# usb_lir2456_charger.net
KiCad netlist of a schematic drawn in EAGLE
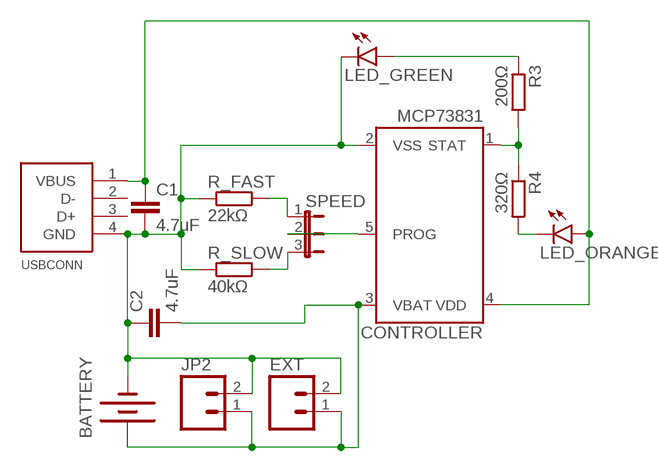
[diagram p0: schematic, sheet 1]

(export (version "E")
  (design (tool "Eeschema 10.0.6"))
  (components
    (comp (ref "BATTERY")
      (value "BATTERY20PTH")
      (footprint "eagle-import:BATTCOM_20MM_PTH")
      (libsource (lib "eagle-import") (part "BATTERY20PTH"))
    )
    (comp (ref "C1")
      (value "4.7uF")
      (footprint "eagle-import:C0805")
      (libsource (lib "eagle-import") (part "C"))
    )
    (comp (ref "C2")
      (value "4.7uF")
      (footprint "eagle-import:C0805")
      (libsource (lib "eagle-import") (part "C"))
    )
    (comp (ref "CONTROLLER")
      (value "MCP73831")
      (footprint "eagle-import:SOT23-5")
      (libsource (lib "eagle-import") (part "MCP73831"))
    )
    (comp (ref "EXT")
      (value "M02PTH")
      (footprint "eagle-import:1X02")
      (libsource (lib "eagle-import") (part "M02PTH"))
    )
    (comp (ref "JP2")
      (value "M02JST-PTH-VERT")
      (footprint "eagle-import:JST-2-PTH-VERT")
      (libsource (lib "eagle-import") (part "M02JST-PTH-VERT"))
    )
    (comp (ref "LED_GREEN")
      (value "LED0603")
      (footprint "eagle-import:LED-0603")
      (libsource (lib "eagle-import") (part "LED0603"))
    )
    (comp (ref "LED_ORANGE")
      (value "LED0603")
      (footprint "eagle-import:LED-0603")
      (libsource (lib "eagle-import") (part "LED0603"))
    )
    (comp (ref "R3")
      (value "200Ω")
      (footprint "eagle-import:R0805")
      (libsource (lib "eagle-import") (part "R"))
    )
    (comp (ref "R4")
      (value "320Ω")
      (footprint "eagle-import:R0805")
      (libsource (lib "eagle-import") (part "R"))
    )
    (comp (ref "R_FAST")
      (value "22kΩ")
      (footprint "eagle-import:R0805")
      (libsource (lib "eagle-import") (part "R"))
    )
    (comp (ref "R_SLOW")
      (value "40kΩ")
      (footprint "eagle-import:R0805")
      (libsource (lib "eagle-import") (part "R"))
    )
    (comp (ref "SPEED")
      (value "JP2E")
      (footprint "eagle-import:JP2")
      (libsource (lib "eagle-import") (part "JP2E"))
    )
    (comp (ref "USBCONN")
      (value "USB-CON-4PIN")
      (footprint "eagle-import:USB-MALE-A-PCB")
      (libsource (lib "eagle-import") (part "USB-CON-4PIN"))
    )
  )
  (nets
    (net (code "1") (name "Net-(BATTERY-+)") (class "Default")
      (node (ref "BATTERY") (pin "1") (pinfunction "+_1") (pintype "power_in"))
      (node (ref "C2") (pin "2") (pinfunction "2_2") (pintype "passive"))
      (node (ref "CONTROLLER") (pin "3") (pinfunction "VBAT_3") (pintype "power_in"))
      (node (ref "EXT") (pin "1") (pinfunction "1_1") (pintype "passive"))
      (node (ref "JP2") (pin "1") (pinfunction "1_1") (pintype "passive"))
    )
    (net (code "2") (name "Net-(BATTERY--)") (class "Default")
      (node (ref "BATTERY") (pin "2") (pinfunction "-_2") (pintype "power_in"))
      (node (ref "C1") (pin "2") (pinfunction "2_2") (pintype "passive"))
      (node (ref "C2") (pin "1") (pinfunction "1_1") (pintype "passive"))
      (node (ref "CONTROLLER") (pin "2") (pinfunction "VSS_2") (pintype "power_in"))
      (node (ref "EXT") (pin "2") (pinfunction "2_2") (pintype "passive"))
      (node (ref "JP2") (pin "2") (pinfunction "2_2") (pintype "passive"))
      (node (ref "LED_GREEN") (pin "C") (pinfunction "C_C") (pintype "passive"))
      (node (ref "R_FAST") (pin "1") (pinfunction "1_1") (pintype "passive"))
      (node (ref "R_SLOW") (pin "1") (pinfunction "1_1") (pintype "passive"))
      (node (ref "USBCONN") (pin "4") (pinfunction "GND_4") (pintype "power_in"))
    )
    (net (code "3") (name "Net-(CONTROLLER-PROG)") (class "Default")
      (node (ref "CONTROLLER") (pin "5") (pinfunction "PROG_5") (pintype "input"))
      (node (ref "SPEED") (pin "2") (pinfunction "2_2") (pintype "passive"))
    )
    (net (code "4") (name "Net-(CONTROLLER-STAT)") (class "Default")
      (node (ref "CONTROLLER") (pin "1") (pinfunction "STAT_1") (pintype "output"))
      (node (ref "R3") (pin "2") (pinfunction "2_2") (pintype "passive"))
      (node (ref "R4") (pin "1") (pinfunction "1_1") (pintype "passive"))
    )
    (net (code "5") (name "Net-(CONTROLLER-VDD)") (class "Default")
      (node (ref "C1") (pin "1") (pinfunction "1_1") (pintype "passive"))
      (node (ref "CONTROLLER") (pin "4") (pinfunction "VDD_4") (pintype "power_in"))
      (node (ref "LED_ORANGE") (pin "A") (pinfunction "A_A") (pintype "passive"))
      (node (ref "USBCONN") (pin "1") (pinfunction "VBUS_1") (pintype "power_in"))
    )
    (net (code "6") (name "Net-(LED_GREEN-PadA)") (class "Default")
      (node (ref "LED_GREEN") (pin "A") (pinfunction "A_A") (pintype "passive"))
      (node (ref "R3") (pin "1") (pinfunction "1_1") (pintype "passive"))
    )
    (net (code "7") (name "Net-(LED_ORANGE-PadC)") (class "Default")
      (node (ref "LED_ORANGE") (pin "C") (pinfunction "C_C") (pintype "passive"))
      (node (ref "R4") (pin "2") (pinfunction "2_2") (pintype "passive"))
    )
    (net (code "8") (name "Net-(R_FAST-Pad2)") (class "Default")
      (node (ref "R_FAST") (pin "2") (pinfunction "2_2") (pintype "passive"))
      (node (ref "SPEED") (pin "1") (pinfunction "1_1") (pintype "passive"))
    )
    (net (code "9") (name "Net-(R_SLOW-Pad2)") (class "Default")
      (node (ref "R_SLOW") (pin "2") (pinfunction "2_2") (pintype "passive"))
      (node (ref "SPEED") (pin "3") (pinfunction "3_3") (pintype "passive"))
    )
    (net (code "10") (name "unconnected-(USBCONN-D+-Pad3)") (class "Default")
      (node (ref "USBCONN") (pin "3") (pinfunction "D+_3") (pintype "bidirectional"))
    )
    (net (code "11") (name "unconnected-(USBCONN-D--Pad2)") (class "Default")
      (node (ref "USBCONN") (pin "2") (pinfunction "D-_2") (pintype "bidirectional"))
    )
  )
)
